# Dragon_LowerCase_orig.net
KiCad netlist of a schematic drawn in EAGLE
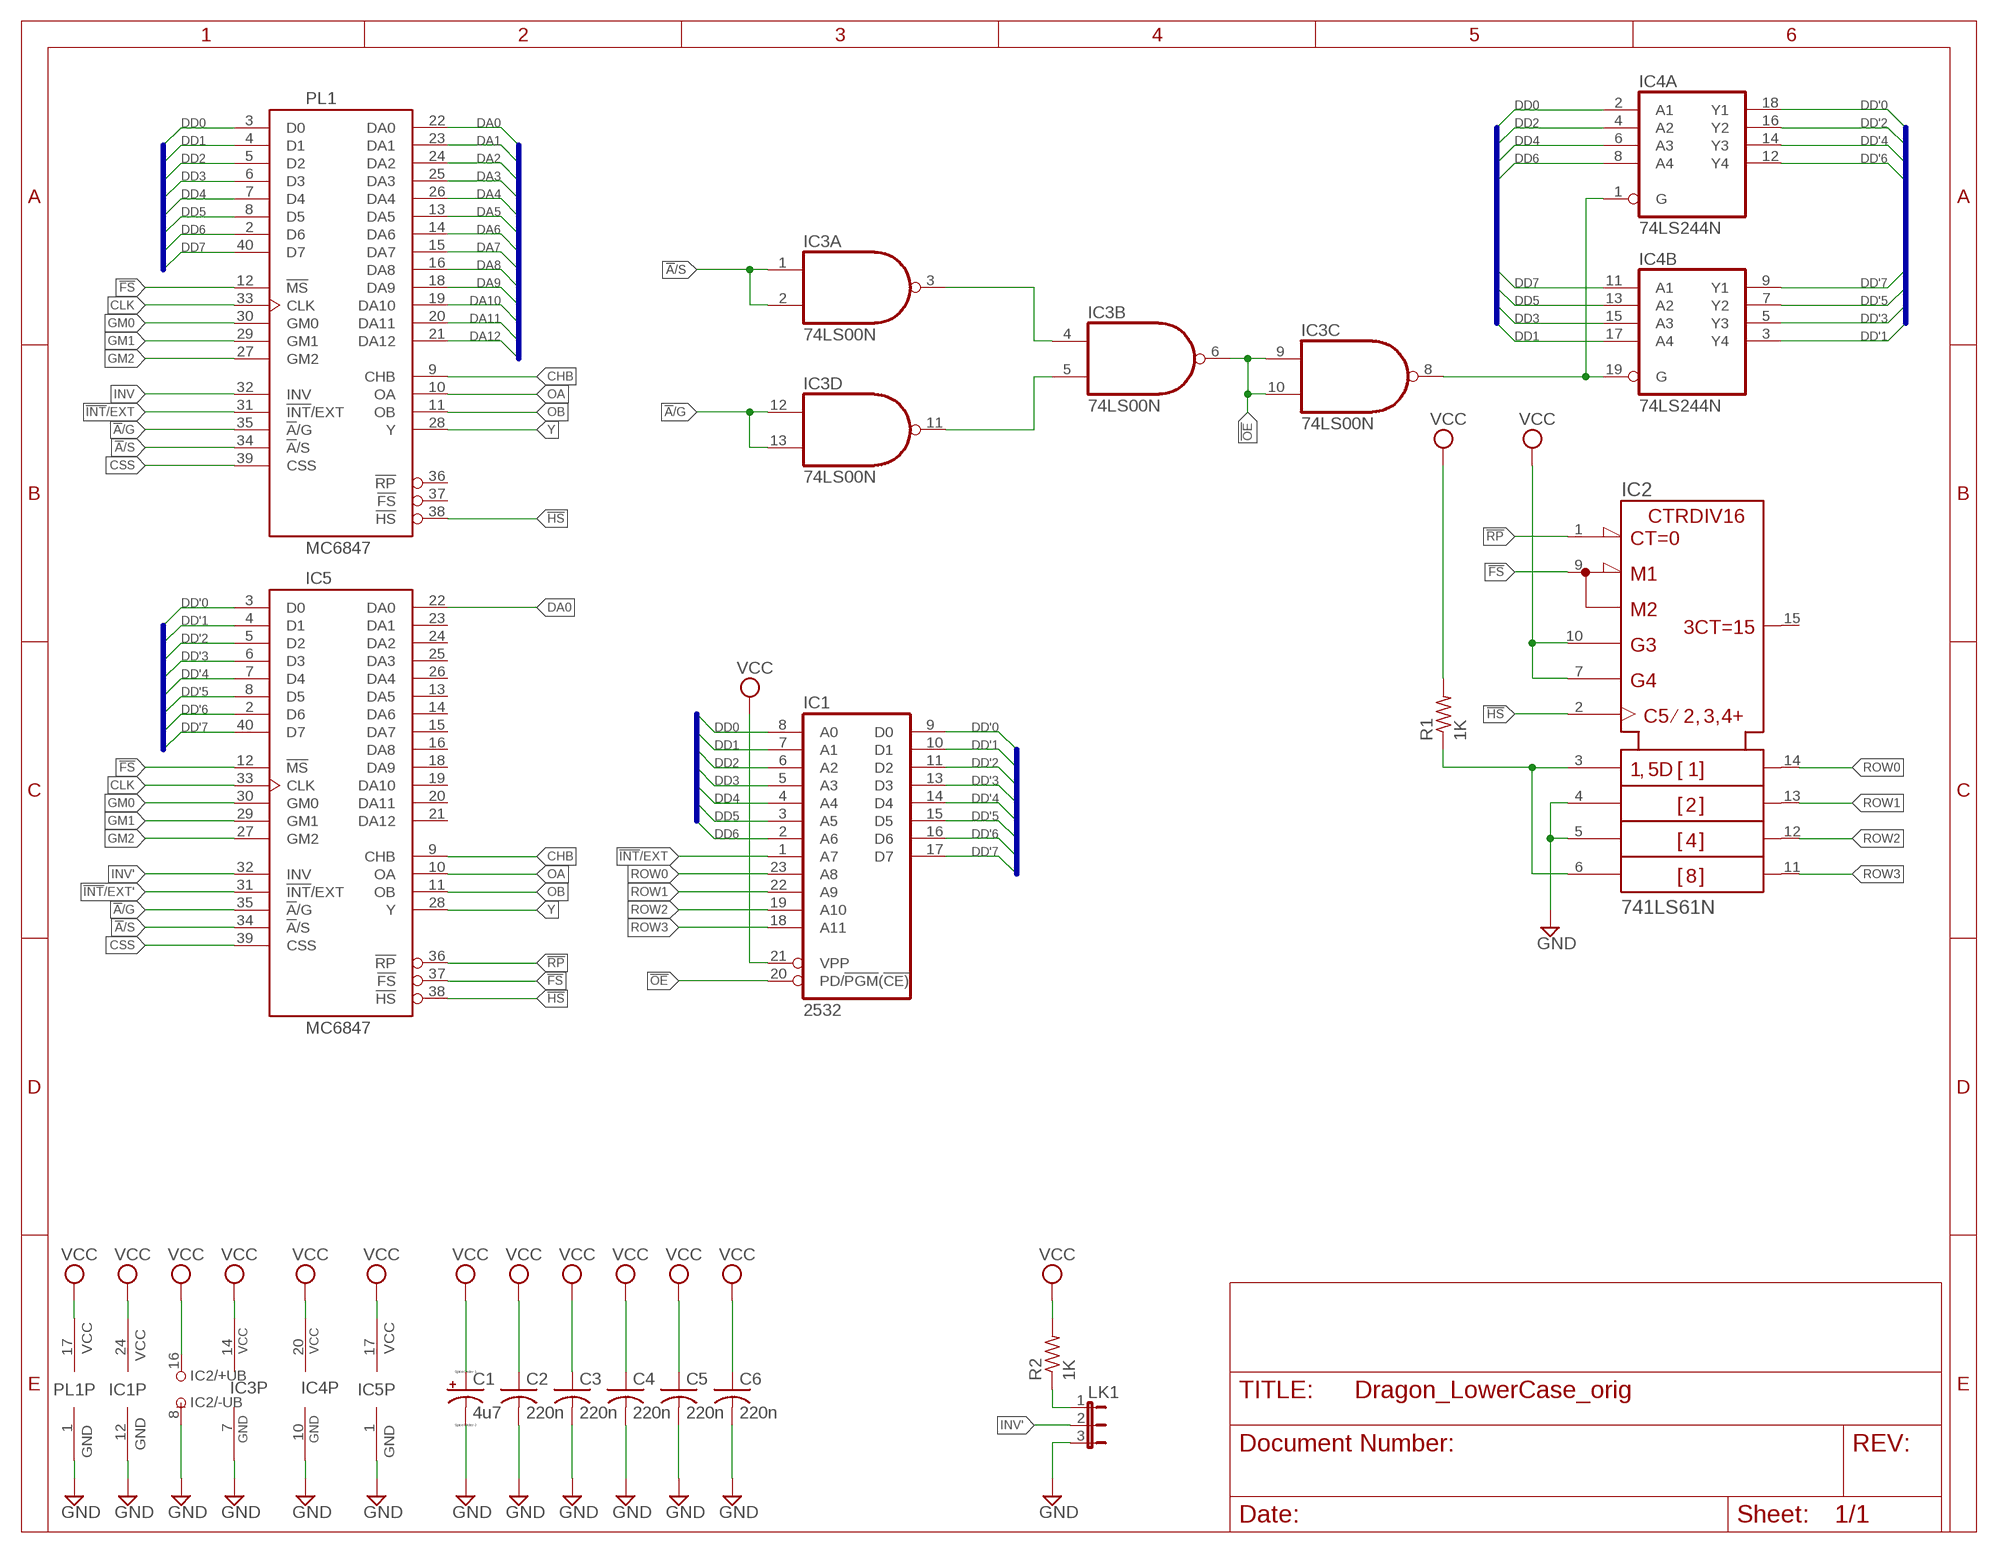
[diagram p0: schematic, sheet 1]

(export (version "E")
  (design (tool "Eeschema 10.0.6"))
  (components
    (comp (ref "C1")
      (value "4u7")
      (footprint "eagle-import:E2,5-5")
      (libsource (lib "eagle-import") (part "CPOL-USE2.5-5"))
    )
    (comp (ref "C2")
      (value "220n")
      (footprint "eagle-import:C025-025X050")
      (libsource (lib "eagle-import") (part "C-US025-025X050"))
    )
    (comp (ref "C3")
      (value "220n")
      (footprint "eagle-import:C025-025X050")
      (libsource (lib "eagle-import") (part "C-US025-025X050"))
    )
    (comp (ref "C4")
      (value "220n")
      (footprint "eagle-import:C025-025X050")
      (libsource (lib "eagle-import") (part "C-US025-025X050"))
    )
    (comp (ref "C5")
      (value "220n")
      (footprint "eagle-import:C025-025X050")
      (libsource (lib "eagle-import") (part "C-US025-025X050"))
    )
    (comp (ref "C6")
      (value "220n")
      (footprint "eagle-import:C025-025X050")
      (libsource (lib "eagle-import") (part "C-US025-025X050"))
    )
    (comp (ref "IC1")
      (value "2532")
      (footprint "eagle-import:DIL24-6-RP")
      (libsource (lib "eagle-import") (part "2532"))
    )
    (comp (ref "IC2")
      (value "741LS61N")
      (footprint "eagle-import:DIL16")
      (libsource (lib "eagle-import") (part "74161N"))
    )
    (comp (ref "IC3")
      (value "74LS00N")
      (footprint "eagle-import:DIL14-RP")
      (libsource (lib "eagle-import") (part "7400NLS"))
    )
    (comp (ref "IC4")
      (value "74LS244N")
      (footprint "eagle-import:DIL20-RP")
      (libsource (lib "eagle-import") (part "74244NLS"))
    )
    (comp (ref "IC5")
      (value "MC6847")
      (footprint "eagle-import:DIL40")
      (libsource (lib "eagle-import") (part "MC6847"))
    )
    (comp (ref "LK1")
      (value "JP2E")
      (footprint "eagle-import:JP2")
      (libsource (lib "eagle-import") (part "JP2E"))
    )
    (comp (ref "PL1")
      (value "MC6847")
      (footprint "eagle-import:DIL40")
      (libsource (lib "eagle-import") (part "MC6847"))
    )
    (comp (ref "R1")
      (value "1K")
      (footprint "eagle-import:0207_10")
      (libsource (lib "eagle-import") (part "R-US_0207/10"))
    )
    (comp (ref "R2")
      (value "1K")
      (footprint "eagle-import:0207_10")
      (libsource (lib "eagle-import") (part "R-US_0207/10"))
    )
  )
  (nets
    (net (code "1") (name "/DA1") (class "Default")
      (node (ref "PL1") (pin "23") (pinfunction "DA1_23") (pintype "output"))
    )
    (net (code "2") (name "/DA2") (class "Default")
      (node (ref "PL1") (pin "24") (pinfunction "DA2_24") (pintype "output"))
    )
    (net (code "3") (name "/DA3") (class "Default")
      (node (ref "PL1") (pin "25") (pinfunction "DA3_25") (pintype "output"))
    )
    (net (code "4") (name "/DA4") (class "Default")
      (node (ref "PL1") (pin "26") (pinfunction "DA4_26") (pintype "output"))
    )
    (net (code "5") (name "/DA5") (class "Default")
      (node (ref "PL1") (pin "13") (pinfunction "DA5_13") (pintype "output"))
    )
    (net (code "6") (name "/DA6") (class "Default")
      (node (ref "PL1") (pin "14") (pinfunction "DA6_14") (pintype "output"))
    )
    (net (code "7") (name "/DA7") (class "Default")
      (node (ref "PL1") (pin "15") (pinfunction "DA7_15") (pintype "output"))
    )
    (net (code "8") (name "/DA8") (class "Default")
      (node (ref "PL1") (pin "16") (pinfunction "DA8_16") (pintype "output"))
    )
    (net (code "9") (name "/DA9") (class "Default")
      (node (ref "PL1") (pin "18") (pinfunction "DA9_18") (pintype "output"))
    )
    (net (code "10") (name "/DA10") (class "Default")
      (node (ref "PL1") (pin "19") (pinfunction "DA10_19") (pintype "output"))
    )
    (net (code "11") (name "/DA11") (class "Default")
      (node (ref "PL1") (pin "20") (pinfunction "DA11_20") (pintype "output"))
    )
    (net (code "12") (name "/DA12") (class "Default")
      (node (ref "PL1") (pin "21") (pinfunction "DA12_21") (pintype "output"))
    )
    (net (code "13") (name "/DD'0") (class "Default")
      (node (ref "IC1") (pin "9") (pinfunction "D0_9") (pintype "bidirectional"))
      (node (ref "IC4") (pin "18") (pinfunction "Y1_18") (pintype "tri_state"))
      (node (ref "IC5") (pin "3") (pinfunction "D0_3") (pintype "input"))
    )
    (net (code "14") (name "/DD'1") (class "Default")
      (node (ref "IC1") (pin "10") (pinfunction "D1_10") (pintype "bidirectional"))
      (node (ref "IC4") (pin "3") (pinfunction "Y4_3") (pintype "tri_state"))
      (node (ref "IC5") (pin "4") (pinfunction "D1_4") (pintype "input"))
    )
    (net (code "15") (name "/DD'2") (class "Default")
      (node (ref "IC1") (pin "11") (pinfunction "D2_11") (pintype "bidirectional"))
      (node (ref "IC4") (pin "16") (pinfunction "Y2_16") (pintype "tri_state"))
      (node (ref "IC5") (pin "5") (pinfunction "D2_5") (pintype "input"))
    )
    (net (code "16") (name "/DD'3") (class "Default")
      (node (ref "IC1") (pin "13") (pinfunction "D3_13") (pintype "bidirectional"))
      (node (ref "IC4") (pin "5") (pinfunction "Y3_5") (pintype "tri_state"))
      (node (ref "IC5") (pin "6") (pinfunction "D3_6") (pintype "input"))
    )
    (net (code "17") (name "/DD'4") (class "Default")
      (node (ref "IC1") (pin "14") (pinfunction "D4_14") (pintype "bidirectional"))
      (node (ref "IC4") (pin "14") (pinfunction "Y3_14") (pintype "tri_state"))
      (node (ref "IC5") (pin "7") (pinfunction "D4_7") (pintype "input"))
    )
    (net (code "18") (name "/DD'5") (class "Default")
      (node (ref "IC1") (pin "15") (pinfunction "D5_15") (pintype "bidirectional"))
      (node (ref "IC4") (pin "7") (pinfunction "Y2_7") (pintype "tri_state"))
      (node (ref "IC5") (pin "8") (pinfunction "D5_8") (pintype "input"))
    )
    (net (code "19") (name "/DD'6") (class "Default")
      (node (ref "IC1") (pin "16") (pinfunction "D6_16") (pintype "bidirectional"))
      (node (ref "IC4") (pin "12") (pinfunction "Y4_12") (pintype "tri_state"))
      (node (ref "IC5") (pin "2") (pinfunction "D6_2") (pintype "input"))
    )
    (net (code "20") (name "/DD'7") (class "Default")
      (node (ref "IC1") (pin "17") (pinfunction "D7_17") (pintype "bidirectional"))
      (node (ref "IC4") (pin "9") (pinfunction "Y1_9") (pintype "tri_state"))
      (node (ref "IC5") (pin "40") (pinfunction "D7_40") (pintype "input"))
    )
    (net (code "21") (name "/DD0") (class "Default")
      (node (ref "IC1") (pin "8") (pinfunction "A0_8") (pintype "input"))
      (node (ref "IC4") (pin "2") (pinfunction "A1_2") (pintype "input"))
      (node (ref "PL1") (pin "3") (pinfunction "D0_3") (pintype "input"))
    )
    (net (code "22") (name "/DD1") (class "Default")
      (node (ref "IC1") (pin "7") (pinfunction "A1_7") (pintype "input"))
      (node (ref "IC4") (pin "17") (pinfunction "A4_17") (pintype "input"))
      (node (ref "PL1") (pin "4") (pinfunction "D1_4") (pintype "input"))
    )
    (net (code "23") (name "/DD2") (class "Default")
      (node (ref "IC1") (pin "6") (pinfunction "A2_6") (pintype "input"))
      (node (ref "IC4") (pin "4") (pinfunction "A2_4") (pintype "input"))
      (node (ref "PL1") (pin "5") (pinfunction "D2_5") (pintype "input"))
    )
    (net (code "24") (name "/DD3") (class "Default")
      (node (ref "IC1") (pin "5") (pinfunction "A3_5") (pintype "input"))
      (node (ref "IC4") (pin "15") (pinfunction "A3_15") (pintype "input"))
      (node (ref "PL1") (pin "6") (pinfunction "D3_6") (pintype "input"))
    )
    (net (code "25") (name "/DD4") (class "Default")
      (node (ref "IC1") (pin "4") (pinfunction "A4_4") (pintype "input"))
      (node (ref "IC4") (pin "6") (pinfunction "A3_6") (pintype "input"))
      (node (ref "PL1") (pin "7") (pinfunction "D4_7") (pintype "input"))
    )
    (net (code "26") (name "/DD5") (class "Default")
      (node (ref "IC1") (pin "3") (pinfunction "A5_3") (pintype "input"))
      (node (ref "IC4") (pin "13") (pinfunction "A2_13") (pintype "input"))
      (node (ref "PL1") (pin "8") (pinfunction "D5_8") (pintype "input"))
    )
    (net (code "27") (name "/DD6") (class "Default")
      (node (ref "IC1") (pin "2") (pinfunction "A6_2") (pintype "input"))
      (node (ref "IC4") (pin "8") (pinfunction "A4_8") (pintype "input"))
      (node (ref "PL1") (pin "2") (pinfunction "D6_2") (pintype "input"))
    )
    (net (code "28") (name "/DD7") (class "Default")
      (node (ref "IC4") (pin "11") (pinfunction "A1_11") (pintype "input"))
      (node (ref "PL1") (pin "40") (pinfunction "D7_40") (pintype "input"))
    )
    (net (code "29") (name "/~{A}{slash}G") (class "Default")
      (node (ref "IC3") (pin "12") (pinfunction "I0_12") (pintype "input"))
      (node (ref "IC3") (pin "13") (pinfunction "I1_13") (pintype "input"))
      (node (ref "IC5") (pin "35") (pinfunction "~{A}/G_35") (pintype "input"))
      (node (ref "PL1") (pin "35") (pinfunction "~{A}/G_35") (pintype "input"))
    )
    (net (code "30") (name "/~{A}{slash}S") (class "Default")
      (node (ref "IC3") (pin "1") (pinfunction "I0_1") (pintype "input"))
      (node (ref "IC3") (pin "2") (pinfunction "I1_2") (pintype "input"))
      (node (ref "IC5") (pin "34") (pinfunction "~{A}/S_34") (pintype "input"))
      (node (ref "PL1") (pin "34") (pinfunction "~{A}/S_34") (pintype "input"))
    )
    (net (code "31") (name "/~{FS}") (class "Default")
      (node (ref "IC2") (pin "9") (pinfunction "~{LOAD}_9") (pintype "input"))
      (node (ref "IC5") (pin "12") (pinfunction "~{MS}_12") (pintype "input"))
      (node (ref "IC5") (pin "37") (pinfunction "~{FS}_37") (pintype "output"))
      (node (ref "PL1") (pin "12") (pinfunction "~{MS}_12") (pintype "input"))
    )
    (net (code "32") (name "/~{HS}") (class "Default")
      (node (ref "IC2") (pin "2") (pinfunction "CLK_2") (pintype "input"))
      (node (ref "IC5") (pin "38") (pinfunction "~{HS}_38") (pintype "output"))
      (node (ref "PL1") (pin "38") (pinfunction "~{HS}_38") (pintype "output"))
    )
    (net (code "33") (name "/~{INT}{slash}EXT") (class "Default")
      (node (ref "IC1") (pin "1") (pinfunction "A7_1") (pintype "input"))
      (node (ref "PL1") (pin "31") (pinfunction "~{INT}/EXT_31") (pintype "input"))
    )
    (net (code "34") (name "/~{INT}{slash}EXT'") (class "Default")
      (node (ref "IC3") (pin "3") (pinfunction "O_3") (pintype "output"))
      (node (ref "IC3") (pin "4") (pinfunction "I0_4") (pintype "input"))
      (node (ref "IC5") (pin "31") (pinfunction "~{INT}/EXT_31") (pintype "input"))
    )
    (net (code "35") (name "/~{OE}") (class "Default")
      (node (ref "IC1") (pin "20") (pinfunction "PD/~{PGM}(~{CE})_20") (pintype "input"))
      (node (ref "IC3") (pin "10") (pinfunction "I1_10") (pintype "input"))
      (node (ref "IC3") (pin "6") (pinfunction "O_6") (pintype "output"))
      (node (ref "IC3") (pin "9") (pinfunction "I0_9") (pintype "input"))
    )
    (net (code "36") (name "/~{RP}") (class "Default")
      (node (ref "IC2") (pin "1") (pinfunction "~{CLR}_1") (pintype "input"))
      (node (ref "IC5") (pin "36") (pinfunction "~{RP}_36") (pintype "output"))
    )
    (net (code "37") (name "CHB") (class "Default")
      (node (ref "IC5") (pin "9") (pinfunction "CHB_9") (pintype "output"))
      (node (ref "PL1") (pin "9") (pinfunction "CHB_9") (pintype "output"))
    )
    (net (code "38") (name "CLK") (class "Default")
      (node (ref "IC5") (pin "33") (pinfunction "CLK_33") (pintype "input"))
      (node (ref "PL1") (pin "33") (pinfunction "CLK_33") (pintype "input"))
    )
    (net (code "39") (name "CSS") (class "Default")
      (node (ref "IC5") (pin "39") (pinfunction "CSS_39") (pintype "input"))
      (node (ref "PL1") (pin "39") (pinfunction "CSS_39") (pintype "input"))
    )
    (net (code "40") (name "DA0") (class "Default")
      (node (ref "IC5") (pin "22") (pinfunction "DA0_22") (pintype "output"))
      (node (ref "PL1") (pin "22") (pinfunction "DA0_22") (pintype "output"))
    )
    (net (code "41") (name "GM0") (class "Default")
      (node (ref "IC5") (pin "30") (pinfunction "GM0_30") (pintype "input"))
      (node (ref "PL1") (pin "30") (pinfunction "GM0_30") (pintype "input"))
    )
    (net (code "42") (name "GM1") (class "Default")
      (node (ref "IC5") (pin "29") (pinfunction "GM1_29") (pintype "input"))
      (node (ref "PL1") (pin "29") (pinfunction "GM1_29") (pintype "input"))
    )
    (net (code "43") (name "GM2") (class "Default")
      (node (ref "IC5") (pin "27") (pinfunction "GM2_27") (pintype "input"))
      (node (ref "PL1") (pin "27") (pinfunction "GM2_27") (pintype "input"))
    )
    (net (code "44") (name "GND") (class "Default")
      (node (ref "C1") (pin "-") (pinfunction "-_-") (pintype "passive"))
      (node (ref "C2") (pin "2") (pinfunction "2_2") (pintype "passive"))
      (node (ref "C3") (pin "2") (pinfunction "2_2") (pintype "passive"))
      (node (ref "C4") (pin "2") (pinfunction "2_2") (pintype "passive"))
      (node (ref "C5") (pin "2") (pinfunction "2_2") (pintype "passive"))
      (node (ref "C6") (pin "2") (pinfunction "2_2") (pintype "passive"))
      (node (ref "IC1") (pin "12") (pinfunction "GND_12") (pintype "power_in"))
      (node (ref "IC2") (pin "4") (pinfunction "B_4") (pintype "input"))
      (node (ref "IC2") (pin "5") (pinfunction "C_5") (pintype "input"))
      (node (ref "IC2") (pin "8") (pinfunction "-UB_8") (pintype "power_in"))
      (node (ref "IC3") (pin "7") (pinfunction "GND_7") (pintype "power_in"))
      (node (ref "IC4") (pin "10") (pinfunction "GND_10") (pintype "power_in"))
      (node (ref "IC5") (pin "1") (pinfunction "GND_1") (pintype "power_in"))
      (node (ref "LK1") (pin "3") (pinfunction "3_3") (pintype "passive"))
      (node (ref "PL1") (pin "1") (pinfunction "GND_1") (pintype "power_in"))
    )
    (net (code "45") (name "INV") (class "Default")
      (node (ref "PL1") (pin "32") (pinfunction "INV_32") (pintype "input"))
    )
    (net (code "46") (name "INV'") (class "Default")
      (node (ref "IC5") (pin "32") (pinfunction "INV_32") (pintype "input"))
      (node (ref "LK1") (pin "2") (pinfunction "2_2") (pintype "passive"))
    )
    (net (code "47") (name "Net-(IC2C-A)") (class "Default")
      (node (ref "IC2") (pin "3") (pinfunction "A_3") (pintype "input"))
      (node (ref "IC2") (pin "6") (pinfunction "D_6") (pintype "input"))
      (node (ref "R1") (pin "1") (pinfunction "1_1") (pintype "passive"))
    )
    (net (code "48") (name "Net-(IC3B-I1)") (class "Default")
      (node (ref "IC3") (pin "11") (pinfunction "O_11") (pintype "output"))
      (node (ref "IC3") (pin "5") (pinfunction "I1_5") (pintype "input"))
    )
    (net (code "49") (name "Net-(IC3C-O)") (class "Default")
      (node (ref "IC3") (pin "8") (pinfunction "O_8") (pintype "output"))
      (node (ref "IC4") (pin "1") (pinfunction "G_1") (pintype "input"))
      (node (ref "IC4") (pin "19") (pinfunction "G_19") (pintype "input"))
    )
    (net (code "50") (name "Net-(LK1-Pad1)") (class "Default")
      (node (ref "LK1") (pin "1") (pinfunction "1_1") (pintype "passive"))
      (node (ref "R2") (pin "1") (pinfunction "1_1") (pintype "passive"))
    )
    (net (code "51") (name "OA") (class "Default")
      (node (ref "IC5") (pin "10") (pinfunction "OA_10") (pintype "output"))
      (node (ref "PL1") (pin "10") (pinfunction "OA_10") (pintype "output"))
    )
    (net (code "52") (name "OB") (class "Default")
      (node (ref "IC5") (pin "11") (pinfunction "OB_11") (pintype "output"))
      (node (ref "PL1") (pin "11") (pinfunction "OB_11") (pintype "output"))
    )
    (net (code "53") (name "ROW0") (class "Default")
      (node (ref "IC1") (pin "23") (pinfunction "A8_23") (pintype "input"))
      (node (ref "IC2") (pin "14") (pinfunction "QA_14") (pintype "output"))
    )
    (net (code "54") (name "ROW1") (class "Default")
      (node (ref "IC1") (pin "22") (pinfunction "A9_22") (pintype "input"))
      (node (ref "IC2") (pin "13") (pinfunction "QB_13") (pintype "output"))
    )
    (net (code "55") (name "ROW2") (class "Default")
      (node (ref "IC1") (pin "19") (pinfunction "A10_19") (pintype "input"))
      (node (ref "IC2") (pin "12") (pinfunction "QC_12") (pintype "output"))
    )
    (net (code "56") (name "ROW3") (class "Default")
      (node (ref "IC1") (pin "18") (pinfunction "A11_18") (pintype "input"))
      (node (ref "IC2") (pin "11") (pinfunction "QD_11") (pintype "output"))
    )
    (net (code "57") (name "VCC") (class "Default")
      (node (ref "C1") (pin "+") (pinfunction "+_+") (pintype "passive"))
      (node (ref "C2") (pin "1") (pinfunction "1_1") (pintype "passive"))
      (node (ref "C3") (pin "1") (pinfunction "1_1") (pintype "passive"))
      (node (ref "C4") (pin "1") (pinfunction "1_1") (pintype "passive"))
      (node (ref "C5") (pin "1") (pinfunction "1_1") (pintype "passive"))
      (node (ref "C6") (pin "1") (pinfunction "1_1") (pintype "passive"))
      (node (ref "IC1") (pin "21") (pinfunction "VPP_21") (pintype "input"))
      (node (ref "IC1") (pin "24") (pinfunction "VCC_24") (pintype "power_in"))
      (node (ref "IC2") (pin "10") (pinfunction "ENT_10") (pintype "input"))
      (node (ref "IC2") (pin "16") (pinfunction "+UB_16") (pintype "power_in"))
      (node (ref "IC2") (pin "7") (pinfunction "ENP_7") (pintype "input"))
      (node (ref "IC3") (pin "14") (pinfunction "VCC_14") (pintype "power_in"))
      (node (ref "IC4") (pin "20") (pinfunction "VCC_20") (pintype "power_in"))
      (node (ref "IC5") (pin "17") (pinfunction "VCC_17") (pintype "power_in"))
      (node (ref "PL1") (pin "17") (pinfunction "VCC_17") (pintype "power_in"))
      (node (ref "R1") (pin "2") (pinfunction "2_2") (pintype "passive"))
      (node (ref "R2") (pin "2") (pinfunction "2_2") (pintype "passive"))
    )
    (net (code "58") (name "Y") (class "Default")
      (node (ref "IC5") (pin "28") (pinfunction "Y_28") (pintype "output"))
      (node (ref "PL1") (pin "28") (pinfunction "Y_28") (pintype "output"))
    )
    (net (code "59") (name "unconnected-(IC2C-RCO-Pad15)") (class "Default")
      (node (ref "IC2") (pin "15") (pinfunction "RCO_15") (pintype "output"))
    )
    (net (code "60") (name "unconnected-(IC5A-DA1-Pad23)") (class "Default")
      (node (ref "IC5") (pin "23") (pinfunction "DA1_23") (pintype "output"))
    )
    (net (code "61") (name "unconnected-(IC5A-DA2-Pad24)") (class "Default")
      (node (ref "IC5") (pin "24") (pinfunction "DA2_24") (pintype "output"))
    )
    (net (code "62") (name "unconnected-(IC5A-DA3-Pad25)") (class "Default")
      (node (ref "IC5") (pin "25") (pinfunction "DA3_25") (pintype "output"))
    )
    (net (code "63") (name "unconnected-(IC5A-DA4-Pad26)") (class "Default")
      (node (ref "IC5") (pin "26") (pinfunction "DA4_26") (pintype "output"))
    )
    (net (code "64") (name "unconnected-(IC5A-DA5-Pad13)") (class "Default")
      (node (ref "IC5") (pin "13") (pinfunction "DA5_13") (pintype "output"))
    )
    (net (code "65") (name "unconnected-(IC5A-DA6-Pad14)") (class "Default")
      (node (ref "IC5") (pin "14") (pinfunction "DA6_14") (pintype "output"))
    )
    (net (code "66") (name "unconnected-(IC5A-DA7-Pad15)") (class "Default")
      (node (ref "IC5") (pin "15") (pinfunction "DA7_15") (pintype "output"))
    )
    (net (code "67") (name "unconnected-(IC5A-DA8-Pad16)") (class "Default")
      (node (ref "IC5") (pin "16") (pinfunction "DA8_16") (pintype "output"))
    )
    (net (code "68") (name "unconnected-(IC5A-DA9-Pad18)") (class "Default")
      (node (ref "IC5") (pin "18") (pinfunction "DA9_18") (pintype "output"))
    )
    (net (code "69") (name "unconnected-(IC5A-DA10-Pad19)") (class "Default")
      (node (ref "IC5") (pin "19") (pinfunction "DA10_19") (pintype "output"))
    )
    (net (code "70") (name "unconnected-(IC5A-DA11-Pad20)") (class "Default")
      (node (ref "IC5") (pin "20") (pinfunction "DA11_20") (pintype "output"))
    )
    (net (code "71") (name "unconnected-(IC5A-DA12-Pad21)") (class "Default")
      (node (ref "IC5") (pin "21") (pinfunction "DA12_21") (pintype "output"))
    )
    (net (code "72") (name "unconnected-(PL1A-~{FS}-Pad37)") (class "Default")
      (node (ref "PL1") (pin "37") (pinfunction "~{FS}_37") (pintype "output"))
    )
    (net (code "73") (name "unconnected-(PL1A-~{RP}-Pad36)") (class "Default")
      (node (ref "PL1") (pin "36") (pinfunction "~{RP}_36") (pintype "output"))
    )
  )
)
